# AD8232_Heart_Rate_Monitor.net
KiCad netlist of a schematic drawn in EAGLE
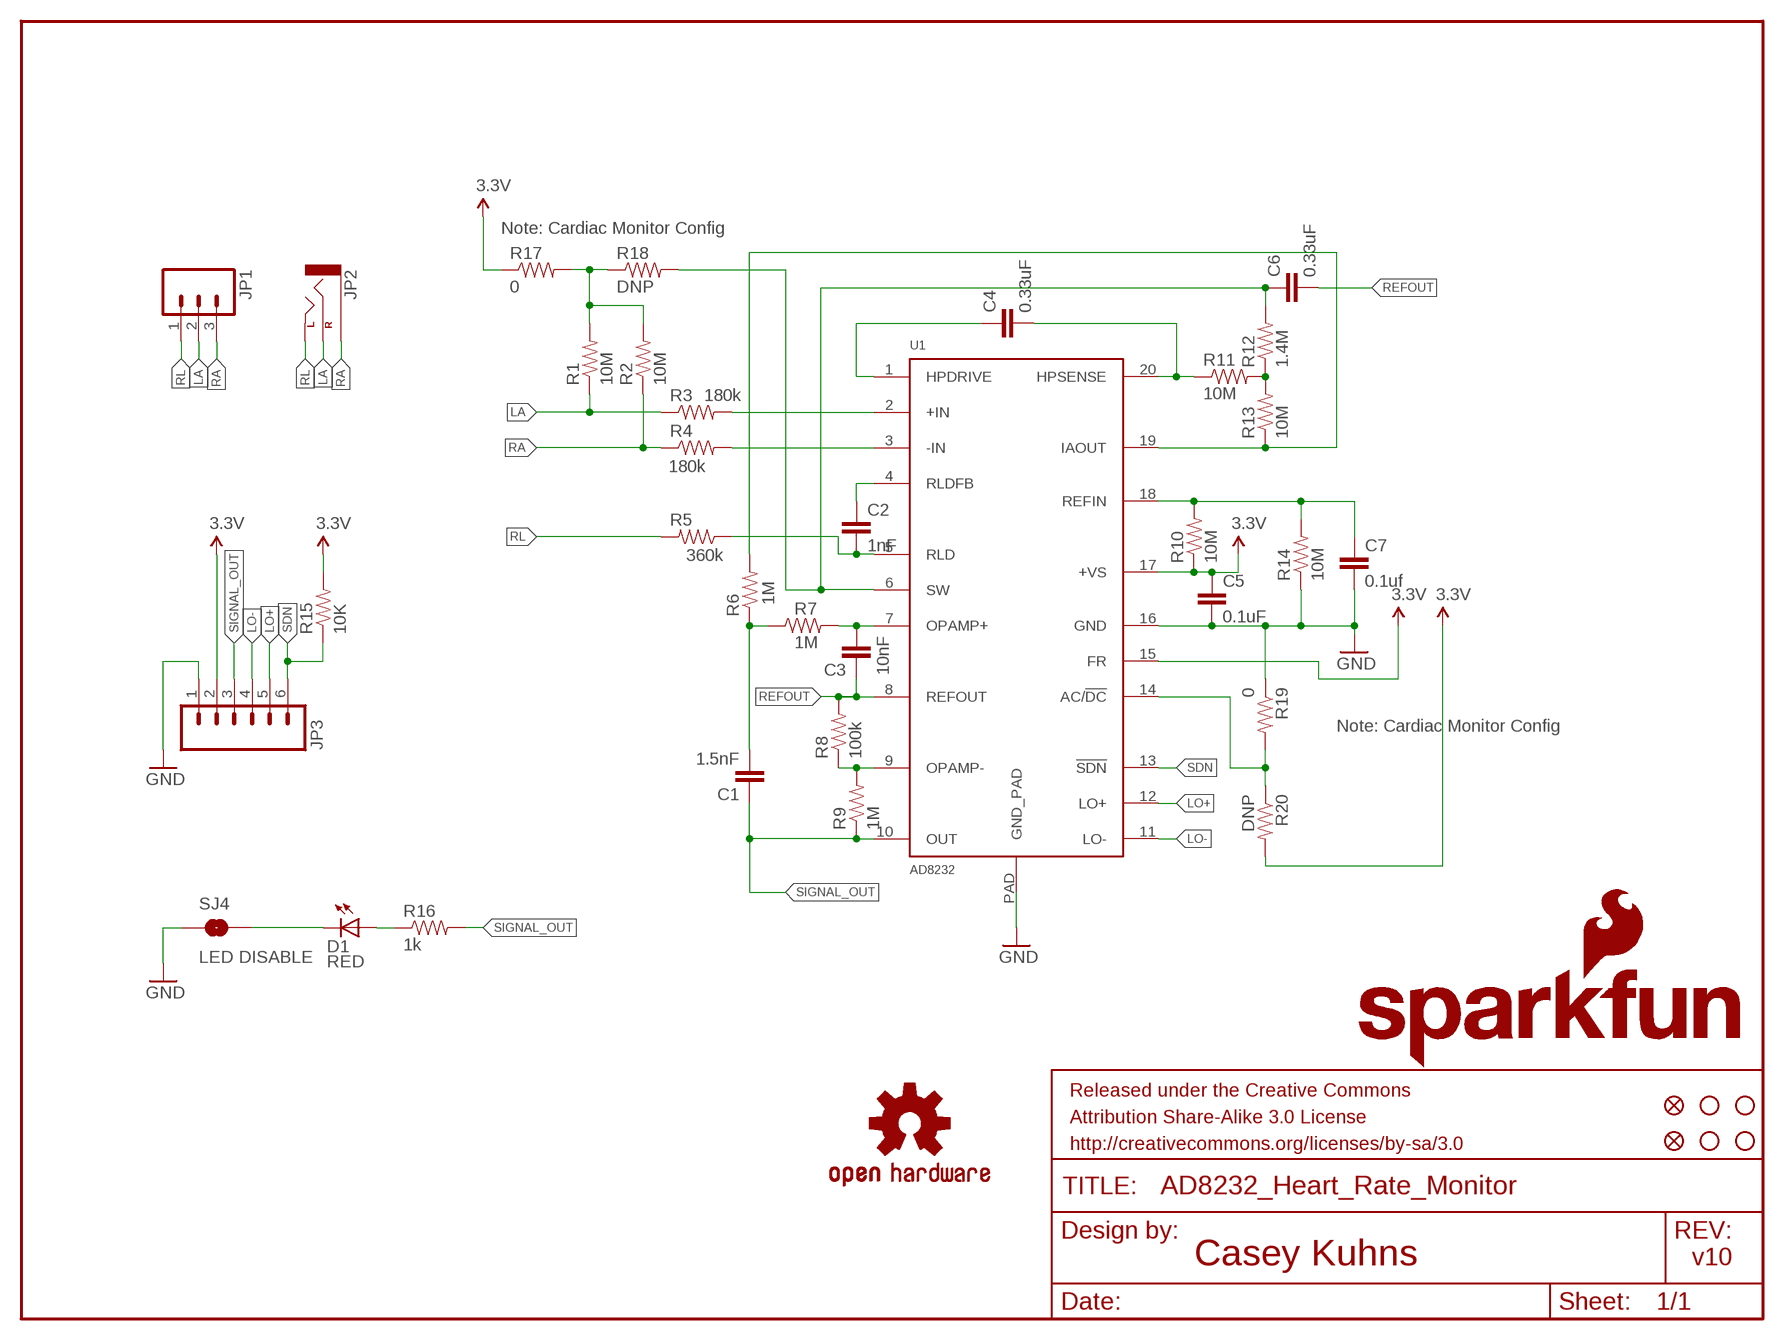
[diagram p0: schematic, sheet 1]

(export (version "E")
  (design (tool "Eeschema 10.0.6"))
  (components
    (comp (ref "C1")
      (value "1.5nF")
      (footprint "eagle-import:0603-CAP")
      (libsource (lib "eagle-import") (part "CAP0603-CAP"))
    )
    (comp (ref "C2")
      (value "1nF")
      (footprint "eagle-import:0603-CAP")
      (libsource (lib "eagle-import") (part "CAP0603-CAP"))
    )
    (comp (ref "C3")
      (value "10nF")
      (footprint "eagle-import:0603-CAP")
      (libsource (lib "eagle-import") (part "CAP0603-CAP"))
    )
    (comp (ref "C4")
      (value "0.33uF")
      (footprint "eagle-import:0805")
      (libsource (lib "eagle-import") (part "CAP0805"))
    )
    (comp (ref "C5")
      (value "0.1uF")
      (footprint "eagle-import:0603-CAP")
      (libsource (lib "eagle-import") (part "CAP0603-CAP"))
    )
    (comp (ref "C6")
      (value "0.33uF")
      (footprint "eagle-import:0805")
      (libsource (lib "eagle-import") (part "CAP0805"))
    )
    (comp (ref "C7")
      (value "0.1uf")
      (footprint "eagle-import:0603-CAP")
      (libsource (lib "eagle-import") (part "CAP0603-CAP"))
    )
    (comp (ref "D1")
      (value "RED")
      (footprint "eagle-import:LED-0603")
      (libsource (lib "eagle-import") (part "LED-RED0603"))
    )
    (comp (ref "FID1")
      (value "FIDUCIAL1X2")
      (footprint "eagle-import:FIDUCIAL-1X2")
      (libsource (lib "eagle-import") (part "FIDUCIAL1X2"))
    )
    (comp (ref "FID2")
      (value "FIDUCIAL1X2")
      (footprint "eagle-import:FIDUCIAL-1X2")
      (libsource (lib "eagle-import") (part "FIDUCIAL1X2"))
    )
    (comp (ref "FRAME1")
      (value "FRAME-LETTER")
      (footprint "eagle-import:CREATIVE_COMMONS")
      (libsource (lib "eagle-import") (part "FRAME-LETTER"))
    )
    (comp (ref "JP1")
      (value "M03PTH")
      (footprint "eagle-import:1X03")
      (libsource (lib "eagle-import") (part "M03PTH"))
    )
    (comp (ref "JP2")
      (value "AUDIO-JACKSMD2")
      (footprint "eagle-import:AUDIO-JACK-3.5MM-SMD")
      (libsource (lib "eagle-import") (part "AUDIO-JACKSMD2"))
    )
    (comp (ref "JP3")
      (value "M06SIP")
      (footprint "eagle-import:1X06")
      (libsource (lib "eagle-import") (part "M06SIP"))
    )
    (comp (ref "LOGO1")
      (value "OSHW-LOGOS")
      (footprint "eagle-import:OSHW-LOGO-S")
      (libsource (lib "eagle-import") (part "OSHW-LOGOS"))
    )
    (comp (ref "LOGO2")
      (value "SFE_LOGO_NAME_FLAME.1_INCH")
      (footprint "eagle-import:SFE_LOGO_NAME_FLAME_.1")
      (libsource (lib "eagle-import") (part "SFE_LOGO_NAME_FLAME.1_INCH"))
    )
    (comp (ref "R1")
      (value "10M")
      (footprint "eagle-import:0603-RES")
      (libsource (lib "eagle-import") (part "RESISTOR0603-RES"))
    )
    (comp (ref "R2")
      (value "10M")
      (footprint "eagle-import:0603-RES")
      (libsource (lib "eagle-import") (part "RESISTOR0603-RES"))
    )
    (comp (ref "R3")
      (value "180k")
      (footprint "eagle-import:0603-RES")
      (libsource (lib "eagle-import") (part "RESISTOR0603-RES"))
    )
    (comp (ref "R4")
      (value "180k")
      (footprint "eagle-import:0603-RES")
      (libsource (lib "eagle-import") (part "RESISTOR0603-RES"))
    )
    (comp (ref "R5")
      (value "360k")
      (footprint "eagle-import:0603-RES")
      (libsource (lib "eagle-import") (part "RESISTOR0603-RES"))
    )
    (comp (ref "R6")
      (value "1M")
      (footprint "eagle-import:0603-RES")
      (libsource (lib "eagle-import") (part "RESISTOR0603-RES"))
    )
    (comp (ref "R7")
      (value "1M")
      (footprint "eagle-import:0603-RES")
      (libsource (lib "eagle-import") (part "RESISTOR0603-RES"))
    )
    (comp (ref "R8")
      (value "100k")
      (footprint "eagle-import:0603-RES")
      (libsource (lib "eagle-import") (part "RESISTOR0603-RES"))
    )
    (comp (ref "R9")
      (value "1M")
      (footprint "eagle-import:0603-RES")
      (libsource (lib "eagle-import") (part "RESISTOR0603-RES"))
    )
    (comp (ref "R10")
      (value "10M")
      (footprint "eagle-import:0603-RES")
      (libsource (lib "eagle-import") (part "RESISTOR0603-RES"))
    )
    (comp (ref "R11")
      (value "10M")
      (footprint "eagle-import:0603-RES")
      (libsource (lib "eagle-import") (part "RESISTOR0603-RES"))
    )
    (comp (ref "R12")
      (value "1.4M")
      (footprint "eagle-import:0603-RES")
      (libsource (lib "eagle-import") (part "RESISTOR0603-RES"))
    )
    (comp (ref "R13")
      (value "10M")
      (footprint "eagle-import:0603-RES")
      (libsource (lib "eagle-import") (part "RESISTOR0603-RES"))
    )
    (comp (ref "R14")
      (value "10M")
      (footprint "eagle-import:0603-RES")
      (libsource (lib "eagle-import") (part "RESISTOR0603-RES"))
    )
    (comp (ref "R15")
      (value "10K")
      (footprint "eagle-import:0603-RES")
      (libsource (lib "eagle-import") (part "10KOHM1/10W1%(0603)0603"))
    )
    (comp (ref "R16")
      (value "1k")
      (footprint "eagle-import:0603-RES")
      (libsource (lib "eagle-import") (part "1K-1%"))
    )
    (comp (ref "R17")
      (value "0")
      (footprint "eagle-import:0603")
      (libsource (lib "eagle-import") (part "0OHM1/10W5%(0603)"))
    )
    (comp (ref "R18")
      (value "DNP")
      (footprint "eagle-import:0603")
      (libsource (lib "eagle-import") (part "0OHM1/10W5%(0603)"))
    )
    (comp (ref "R19")
      (value "0")
      (footprint "eagle-import:0603")
      (libsource (lib "eagle-import") (part "0OHM1/10W5%(0603)"))
    )
    (comp (ref "R20")
      (value "DNP")
      (footprint "eagle-import:0603")
      (libsource (lib "eagle-import") (part "0OHM1/10W5%(0603)"))
    )
    (comp (ref "SJ4")
      (value "LED DISABLE")
      (footprint "eagle-import:SJ_2S-TRACE")
      (libsource (lib "eagle-import") (part "SOLDERJUMPERTRACE"))
    )
    (comp (ref "STANDOFF1")
      (value "STAND-OFF")
      (footprint "eagle-import:STAND-OFF")
      (libsource (lib "eagle-import") (part "STAND-OFF"))
    )
    (comp (ref "STANDOFF2")
      (value "STAND-OFF")
      (footprint "eagle-import:STAND-OFF")
      (libsource (lib "eagle-import") (part "STAND-OFF"))
    )
    (comp (ref "STANDOFF3")
      (value "STAND-OFF")
      (footprint "eagle-import:STAND-OFF")
      (libsource (lib "eagle-import") (part "STAND-OFF"))
    )
    (comp (ref "STANDOFF4")
      (value "STAND-OFF")
      (footprint "eagle-import:STAND-OFF")
      (libsource (lib "eagle-import") (part "STAND-OFF"))
    )
    (comp (ref "U1")
      (value "AD8232")
      (footprint "eagle-import:LFCSP_20")
      (libsource (lib "eagle-import") (part "AD8232"))
    )
  )
  (nets
    (net (code "1") (name "3.3V") (class "Default")
      (node (ref "C5") (pin "1") (pinfunction "1_1") (pintype "passive"))
      (node (ref "JP3") (pin "2") (pinfunction "2_2") (pintype "passive"))
      (node (ref "R10") (pin "1") (pinfunction "1_1") (pintype "passive"))
      (node (ref "R15") (pin "2") (pinfunction "2_2") (pintype "passive"))
      (node (ref "R17") (pin "1") (pinfunction "1_1") (pintype "passive"))
      (node (ref "R20") (pin "2") (pinfunction "2_2") (pintype "passive"))
      (node (ref "U1") (pin "15") (pinfunction "FR_15") (pintype "bidirectional"))
      (node (ref "U1") (pin "17") (pinfunction "+VS_17") (pintype "bidirectional"))
    )
    (net (code "2") (name "GND") (class "Default")
      (node (ref "C5") (pin "2") (pinfunction "2_2") (pintype "passive"))
      (node (ref "C7") (pin "2") (pinfunction "2_2") (pintype "passive"))
      (node (ref "JP3") (pin "1") (pinfunction "1_1") (pintype "passive"))
      (node (ref "R14") (pin "1") (pinfunction "1_1") (pintype "passive"))
      (node (ref "R19") (pin "1") (pinfunction "1_1") (pintype "passive"))
      (node (ref "SJ4") (pin "1") (pinfunction "1_1") (pintype "passive"))
      (node (ref "U1") (pin "16") (pinfunction "GND_16") (pintype "bidirectional"))
      (node (ref "U1") (pin "PAD") (pinfunction "GND_PAD_PAD") (pintype "bidirectional"))
    )
    (net (code "3") (name "LA") (class "Default")
      (node (ref "JP1") (pin "2") (pinfunction "2_2") (pintype "passive"))
      (node (ref "JP2") (pin "RING") (pinfunction "RIGHT_RING") (pintype "bidirectional"))
      (node (ref "R1") (pin "1") (pinfunction "1_1") (pintype "passive"))
      (node (ref "R3") (pin "1") (pinfunction "1_1") (pintype "passive"))
    )
    (net (code "4") (name "LO+") (class "Default")
      (node (ref "JP3") (pin "5") (pinfunction "5_5") (pintype "passive"))
      (node (ref "U1") (pin "12") (pinfunction "LO+_12") (pintype "bidirectional"))
    )
    (net (code "5") (name "LO-") (class "Default")
      (node (ref "JP3") (pin "4") (pinfunction "4_4") (pintype "passive"))
      (node (ref "U1") (pin "11") (pinfunction "LO-_11") (pintype "bidirectional"))
    )
    (net (code "6") (name "Net-(C1-Pad2)") (class "Default")
      (node (ref "C1") (pin "2") (pinfunction "2_2") (pintype "passive"))
      (node (ref "R6") (pin "1") (pinfunction "1_1") (pintype "passive"))
      (node (ref "R7") (pin "1") (pinfunction "1_1") (pintype "passive"))
    )
    (net (code "7") (name "Net-(D1-PadA)") (class "Default")
      (node (ref "D1") (pin "A") (pinfunction "A_A") (pintype "passive"))
      (node (ref "R16") (pin "1") (pinfunction "1_1") (pintype "passive"))
    )
    (net (code "8") (name "Net-(D1-PadC)") (class "Default")
      (node (ref "D1") (pin "C") (pinfunction "C_C") (pintype "passive"))
      (node (ref "SJ4") (pin "2") (pinfunction "2_2") (pintype "passive"))
    )
    (net (code "9") (name "Net-(R1-Pad2)") (class "Default")
      (node (ref "R1") (pin "2") (pinfunction "2_2") (pintype "passive"))
      (node (ref "R17") (pin "2") (pinfunction "2_2") (pintype "passive"))
      (node (ref "R18") (pin "1") (pinfunction "1_1") (pintype "passive"))
      (node (ref "R2") (pin "2") (pinfunction "2_2") (pintype "passive"))
    )
    (net (code "10") (name "Net-(R11-Pad2)") (class "Default")
      (node (ref "R11") (pin "2") (pinfunction "2_2") (pintype "passive"))
      (node (ref "R12") (pin "1") (pinfunction "1_1") (pintype "passive"))
      (node (ref "R13") (pin "2") (pinfunction "2_2") (pintype "passive"))
    )
    (net (code "11") (name "Net-(U1-+IN)") (class "Default")
      (node (ref "R3") (pin "2") (pinfunction "2_2") (pintype "passive"))
      (node (ref "U1") (pin "2") (pinfunction "+IN_2") (pintype "bidirectional"))
    )
    (net (code "12") (name "Net-(U1--IN)") (class "Default")
      (node (ref "R4") (pin "2") (pinfunction "2_2") (pintype "passive"))
      (node (ref "U1") (pin "3") (pinfunction "-IN_3") (pintype "bidirectional"))
    )
    (net (code "13") (name "Net-(U1-AC{slash}~{DC})") (class "Default")
      (node (ref "R19") (pin "2") (pinfunction "2_2") (pintype "passive"))
      (node (ref "R20") (pin "1") (pinfunction "1_1") (pintype "passive"))
      (node (ref "U1") (pin "14") (pinfunction "AC/~{DC}_14") (pintype "bidirectional"))
    )
    (net (code "14") (name "Net-(U1-HPDRIVE)") (class "Default")
      (node (ref "C4") (pin "1") (pinfunction "1_1") (pintype "passive"))
      (node (ref "U1") (pin "1") (pinfunction "HPDRIVE_1") (pintype "bidirectional"))
    )
    (net (code "15") (name "Net-(U1-HPSENSE)") (class "Default")
      (node (ref "C4") (pin "2") (pinfunction "2_2") (pintype "passive"))
      (node (ref "R11") (pin "1") (pinfunction "1_1") (pintype "passive"))
      (node (ref "U1") (pin "20") (pinfunction "HPSENSE_20") (pintype "bidirectional"))
    )
    (net (code "16") (name "Net-(U1-IAOUT)") (class "Default")
      (node (ref "R13") (pin "1") (pinfunction "1_1") (pintype "passive"))
      (node (ref "R6") (pin "2") (pinfunction "2_2") (pintype "passive"))
      (node (ref "U1") (pin "19") (pinfunction "IAOUT_19") (pintype "bidirectional"))
    )
    (net (code "17") (name "Net-(U1-OPAMP+)") (class "Default")
      (node (ref "C3") (pin "2") (pinfunction "2_2") (pintype "passive"))
      (node (ref "R7") (pin "2") (pinfunction "2_2") (pintype "passive"))
      (node (ref "U1") (pin "7") (pinfunction "OPAMP+_7") (pintype "bidirectional"))
    )
    (net (code "18") (name "Net-(U1-OPAMP-)") (class "Default")
      (node (ref "R8") (pin "1") (pinfunction "1_1") (pintype "passive"))
      (node (ref "R9") (pin "2") (pinfunction "2_2") (pintype "passive"))
      (node (ref "U1") (pin "9") (pinfunction "OPAMP-_9") (pintype "bidirectional"))
    )
    (net (code "19") (name "Net-(U1-REFIN)") (class "Default")
      (node (ref "C7") (pin "1") (pinfunction "1_1") (pintype "passive"))
      (node (ref "R10") (pin "2") (pinfunction "2_2") (pintype "passive"))
      (node (ref "R14") (pin "2") (pinfunction "2_2") (pintype "passive"))
      (node (ref "U1") (pin "18") (pinfunction "REFIN_18") (pintype "bidirectional"))
    )
    (net (code "20") (name "Net-(U1-RLD)") (class "Default")
      (node (ref "C2") (pin "2") (pinfunction "2_2") (pintype "passive"))
      (node (ref "R5") (pin "1") (pinfunction "1_1") (pintype "passive"))
      (node (ref "U1") (pin "5") (pinfunction "RLD_5") (pintype "bidirectional"))
    )
    (net (code "21") (name "Net-(U1-RLDFB)") (class "Default")
      (node (ref "C2") (pin "1") (pinfunction "1_1") (pintype "passive"))
      (node (ref "U1") (pin "4") (pinfunction "RLDFB_4") (pintype "bidirectional"))
    )
    (net (code "22") (name "Net-(U1-SW)") (class "Default")
      (node (ref "C6") (pin "1") (pinfunction "1_1") (pintype "passive"))
      (node (ref "R12") (pin "2") (pinfunction "2_2") (pintype "passive"))
      (node (ref "R18") (pin "2") (pinfunction "2_2") (pintype "passive"))
      (node (ref "U1") (pin "6") (pinfunction "SW_6") (pintype "bidirectional"))
    )
    (net (code "23") (name "RA") (class "Default")
      (node (ref "JP1") (pin "3") (pinfunction "3_3") (pintype "passive"))
      (node (ref "JP2") (pin "SLEEVE") (pinfunction "SLEEVE_SLEEVE") (pintype "bidirectional"))
      (node (ref "R2") (pin "1") (pinfunction "1_1") (pintype "passive"))
      (node (ref "R4") (pin "1") (pinfunction "1_1") (pintype "passive"))
    )
    (net (code "24") (name "REFOUT") (class "Default")
      (node (ref "C3") (pin "1") (pinfunction "1_1") (pintype "passive"))
      (node (ref "C6") (pin "2") (pinfunction "2_2") (pintype "passive"))
      (node (ref "R8") (pin "2") (pinfunction "2_2") (pintype "passive"))
      (node (ref "U1") (pin "8") (pinfunction "REFOUT_8") (pintype "bidirectional"))
    )
    (net (code "25") (name "RL") (class "Default")
      (node (ref "JP1") (pin "1") (pinfunction "1_1") (pintype "passive"))
      (node (ref "JP2") (pin "TIP") (pinfunction "LEFT_TIP") (pintype "bidirectional"))
      (node (ref "R5") (pin "2") (pinfunction "2_2") (pintype "passive"))
    )
    (net (code "26") (name "SDN") (class "Default")
      (node (ref "JP3") (pin "6") (pinfunction "6_6") (pintype "passive"))
      (node (ref "R15") (pin "1") (pinfunction "1_1") (pintype "passive"))
      (node (ref "U1") (pin "13") (pinfunction "~{SDN}_13") (pintype "bidirectional"))
    )
    (net (code "27") (name "SIGNAL_OUT") (class "Default")
      (node (ref "C1") (pin "1") (pinfunction "1_1") (pintype "passive"))
      (node (ref "JP3") (pin "3") (pinfunction "3_3") (pintype "passive"))
      (node (ref "R16") (pin "2") (pinfunction "2_2") (pintype "passive"))
      (node (ref "R9") (pin "1") (pinfunction "1_1") (pintype "passive"))
      (node (ref "U1") (pin "10") (pinfunction "OUT_10") (pintype "bidirectional"))
    )
  )
)
